# SSM2212_Adapter.net
KiCad netlist of a schematic drawn in Altium Designer
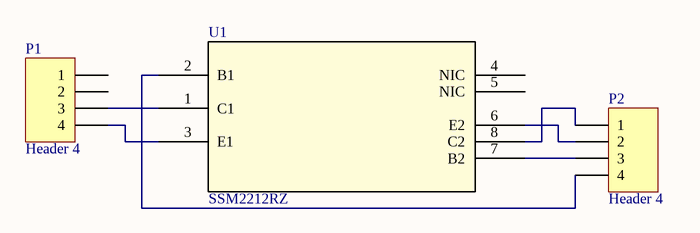
[diagram p0: SSM2212 Adapter.SchDoc]

(export (version "E")
  (design (tool "Eeschema 10.0.6"))
  (components
    (comp (ref "P1")
      (value "Header 4")
      (footprint "HDR1X4")
      (description "Header, 4-Pin")
      (fields (field (name "PUBLISHER") "Altium Limited"))
      (libsource (lib "Miscellaneous Connectors") (part "Header 4"))
    )
    (comp (ref "P2")
      (value "Header 4")
      (footprint "HDR1X4")
      (description "Header, 4-Pin")
      (fields (field (name "PUBLISHER") "Altium Limited"))
      (libsource (lib "") (part "Header 4_1"))
    )
    (comp (ref "U1")
      (value "SSM2212RZ")
      (footprint "SO8_L")
      (description "Imported")
      (libsource (lib "2016-11-28_09-37-58") (part "SSM2212RZ"))
    )
  )
  (nets
    (net (code "1") (name "Net-(U1-B1)") (class "Default")
      (node (ref "P2") (pin "4") (pinfunction "4_4") (pintype "passive"))
      (node (ref "U1") (pin "2") (pinfunction "B1_2") (pintype "passive"))
    )
    (net (code "2") (name "Net-(U1-B2)") (class "Default")
      (node (ref "P2") (pin "3") (pinfunction "3_3") (pintype "passive"))
      (node (ref "U1") (pin "7") (pinfunction "B2_7") (pintype "passive"))
    )
    (net (code "3") (name "Net-(U1-C1)") (class "Default")
      (node (ref "P1") (pin "3") (pinfunction "3_3") (pintype "passive"))
      (node (ref "U1") (pin "1") (pinfunction "C1_1") (pintype "passive"))
    )
    (net (code "4") (name "Net-(U1-C2)") (class "Default")
      (node (ref "P2") (pin "1") (pinfunction "1_1") (pintype "passive"))
      (node (ref "U1") (pin "8") (pinfunction "C2_8") (pintype "passive"))
    )
    (net (code "5") (name "Net-(U1-E1)") (class "Default")
      (node (ref "P1") (pin "4") (pinfunction "4_4") (pintype "passive"))
      (node (ref "U1") (pin "3") (pinfunction "E1_3") (pintype "passive"))
    )
    (net (code "6") (name "Net-(U1-E2)") (class "Default")
      (node (ref "P2") (pin "2") (pinfunction "2_2") (pintype "passive"))
      (node (ref "U1") (pin "6") (pinfunction "E2_6") (pintype "passive"))
    )
    (net (code "7") (name "unconnected-(P1-Pad1)") (class "Default")
      (node (ref "P1") (pin "1") (pinfunction "1_1") (pintype "passive"))
    )
    (net (code "8") (name "unconnected-(P1-Pad2)") (class "Default")
      (node (ref "P1") (pin "2") (pinfunction "2_2") (pintype "passive"))
    )
    (net (code "9") (name "unconnected-(U1-NIC-Pad4)") (class "Default")
      (node (ref "U1") (pin "4") (pinfunction "NIC_4") (pintype "passive"))
    )
    (net (code "10") (name "unconnected-(U1-NIC-Pad5)") (class "Default")
      (node (ref "U1") (pin "5") (pinfunction "NIC_5") (pintype "passive"))
    )
  )
)
